# MCU.net
KiCad netlist of a schematic drawn in Altium Designer
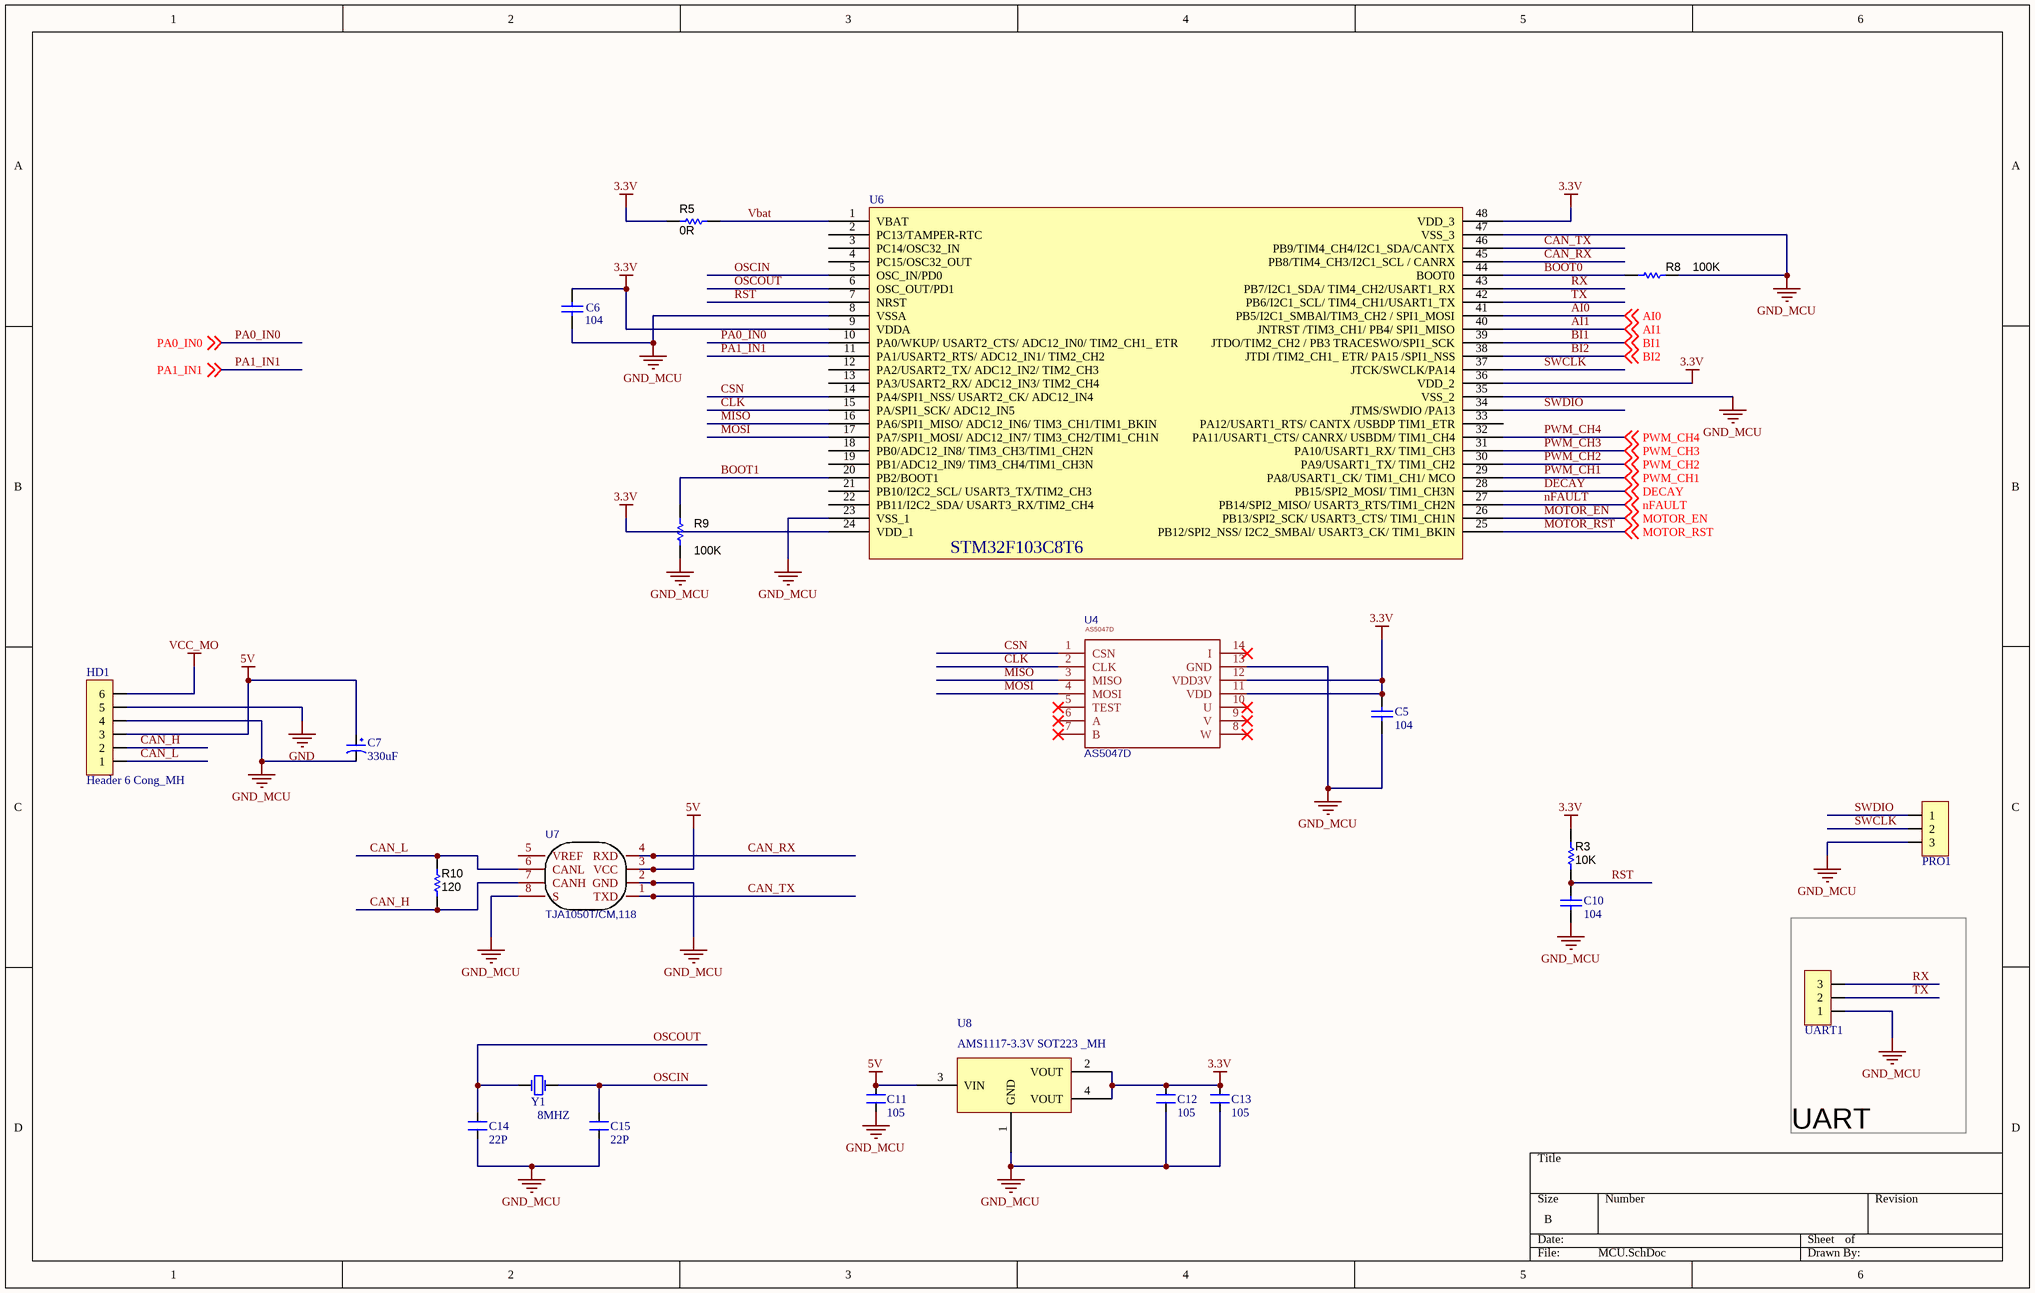
[diagram p0: MCU.SchDoc]

(export (version "E")
  (design (tool "Eeschema 10.0.6"))
  (components
    (comp (ref "C5")
      (value "104")
      (footprint "0805_HV")
      (description "Ceramic Chip Capacitor - Standard")
      (fields (field (name "PUBLISHER") "Altium Limited"))
      (libsource (lib "mySch") (part "Capacitor 0805"))
    )
    (comp (ref "C6")
      (value "104")
      (footprint "0805_HV")
      (description "Ceramic Chip Capacitor - Standard")
      (fields (field (name "PUBLISHER") "Altium Limited"))
      (libsource (lib "mySch") (part "Capacitor 0805"))
    )
    (comp (ref "C7")
      (value "330uF")
      (footprint "TU_NHOM_220uF_25V_MH")
      (description "TU_NHOM_330uF_16V_MH")
      (libsource (lib "MH_DA_THU_VIEN_16122016") (part "TU_NHOM_330uF_16V_MH"))
    )
    (comp (ref "C10")
      (value "104")
      (footprint "0805_HV")
      (description "Ceramic Chip Capacitor - Standard")
      (fields (field (name "PUBLISHER") "Altium Limited"))
      (libsource (lib "mySch") (part "Capacitor 0805"))
    )
    (comp (ref "C11")
      (value "105")
      (footprint "0805_HV")
      (description "Cap SMD")
      (libsource (lib "hatcatbietbay") (part "CM"))
    )
    (comp (ref "C12")
      (value "105")
      (footprint "0805_HV")
      (description "Cap SMD")
      (libsource (lib "hatcatbietbay") (part "CM"))
    )
    (comp (ref "C13")
      (value "105")
      (footprint "0805_HV")
      (description "Cap SMD")
      (libsource (lib "hatcatbietbay") (part "CM"))
    )
    (comp (ref "C14")
      (value "22P")
      (footprint "0805_HV")
      (description "Cap SMD")
      (libsource (lib "hatcatbietbay") (part "CM"))
    )
    (comp (ref "C15")
      (value "22P")
      (footprint "0805_HV")
      (description "Cap SMD")
      (libsource (lib "hatcatbietbay") (part "CM"))
    )
    (comp (ref "HD1")
      (value "Header 6 Cong_MH")
      (footprint "HEADER 6 CONG")
      (description "Header 6P XH2.54 cong")
      (libsource (lib "MH_DA_THU_VIEN_16122016") (part "Header 6 Cong_MH"))
    )
    (comp (ref "PRO1")
      (value "Header 3_MH")
      (footprint "HEADER 3")
      (description "Header 3P XH2.54 thẳng")
      (libsource (lib "") (part "Header 3_MH_1"))
    )
    (comp (ref "R3")
      (value "10K")
      (footprint "0805_HV")
      (description "RES, 100, 1%, 0.1 W, 0402")
      (fields
        (field (name "PARTNUMBER") "ERJ-2RKF1000X")
        (field (name "MANUFACTURER") "Panasonic")
        (field (name "PUBLISHER") "Texas Instruments")
      )
      (libsource (lib "mySch") (part "R nho"))
    )
    (comp (ref "R5")
      (value "0R")
      (footprint "0805_HV")
      (description "RES, 100, 1%, 0.1 W, 0402")
      (fields
        (field (name "PARTNUMBER") "ERJ-2RKF1000X")
        (field (name "MANUFACTURER") "Panasonic")
        (field (name "PUBLISHER") "Texas Instruments")
      )
      (libsource (lib "mySch") (part "R nho"))
    )
    (comp (ref "R8")
      (value "100K")
      (footprint "0805_HV")
      (description "RES, 100, 1%, 0.1 W, 0402")
      (fields
        (field (name "PARTNUMBER") "ERJ-2RKF1000X")
        (field (name "MANUFACTURER") "Panasonic")
        (field (name "PUBLISHER") "Texas Instruments")
      )
      (libsource (lib "mySch") (part "R nho"))
    )
    (comp (ref "R9")
      (value "100K")
      (footprint "0805_HV")
      (description "RES, 100, 1%, 0.1 W, 0402")
      (fields
        (field (name "PARTNUMBER") "ERJ-2RKF1000X")
        (field (name "MANUFACTURER") "Panasonic")
        (field (name "PUBLISHER") "Texas Instruments")
      )
      (libsource (lib "mySch") (part "R nho"))
    )
    (comp (ref "R10")
      (value "120")
      (footprint "0805_HV")
      (description "RES, 100, 1%, 0.1 W, 0402")
      (fields
        (field (name "PARTNUMBER") "ERJ-2RKF1000X")
        (field (name "MANUFACTURER") "Panasonic")
        (field (name "PUBLISHER") "Texas Instruments")
      )
      (libsource (lib "mySch") (part "R nho"))
    )
    (comp (ref "U4")
      (value "AS5047D")
      (footprint "TSSOP14")
      (fields (field (name "BOM_MANUFACTURER PART") "?"))
      (libsource (lib "mySch") (part "AS5047D"))
    )
    (comp (ref "U6")
      (value "STM32F103C8T6 LQFP48 _MH")
      (footprint "LQFP48")
      (libsource (lib "MH_DA_THU_VIEN_16122016") (part "STM32F103C8T6 LQFP48 _MH"))
    )
    (comp (ref "U7")
      (value "TJA1050T/CM,118")
      (footprint "SOP 8")
      (fields (field (name "BOM_SUPPLIER PART") "C6952"))
      (libsource (lib "Schlib1") (part "TJA1050T/CM,118"))
    )
    (comp (ref "U8")
      (value "AMS1117-3.3V SOT223 _MH")
      (footprint "SOT223")
      (libsource (lib "MH_DA_THU_VIEN_16122016") (part "AMS1117-3.3V SOT223 _MH"))
    )
    (comp (ref "UART1")
      (value "Header 3_MH")
      (footprint "HEADER 3")
      (description "Header 3P XH2.54 thẳng")
      (libsource (lib "MH_DA_THU_VIEN_16122016") (part "Header 3_MH"))
    )
    (comp (ref "Y1")
      (value "8MHZ")
      (footprint "XT2")
      (description "Crystal Oscillator")
      (fields (field (name "PUBLISHER") "Altium Limited"))
      (libsource (lib "MH_DA_THU_VIEN_16122016") (part "CRYSTAL_49S DIP_MH"))
    )
  )
  (nets
    (net (code "1") (name "/BOOT0") (class "Default")
      (node (ref "R8") (pin "2") (pinfunction "2_2") (pintype "passive"))
      (node (ref "U6") (pin "44") (pinfunction "BOOT0_44") (pintype "passive"))
    )
    (net (code "2") (name "/BOOT1") (class "Default")
      (node (ref "R9") (pin "1") (pinfunction "1_1") (pintype "passive"))
      (node (ref "U6") (pin "20") (pinfunction "PB2/BOOT1_20") (pintype "passive"))
    )
    (net (code "3") (name "/CAN_H") (class "Default")
      (node (ref "HD1") (pin "2") (pinfunction "2_2") (pintype "passive"))
      (node (ref "R10") (pin "2") (pinfunction "2_2") (pintype "passive"))
      (node (ref "U7") (pin "7") (pinfunction "CANH_7") (pintype "passive"))
    )
    (net (code "4") (name "/CAN_L") (class "Default")
      (node (ref "HD1") (pin "1") (pinfunction "1_1") (pintype "passive"))
      (node (ref "R10") (pin "1") (pinfunction "1_1") (pintype "passive"))
      (node (ref "U7") (pin "6") (pinfunction "CANL_6") (pintype "passive"))
    )
    (net (code "5") (name "/CAN_RX") (class "Default")
      (node (ref "U6") (pin "45") (pinfunction "PB8/TIM4_CH3/I2C1_SCL_/_CANRX_45") (pintype "passive"))
      (node (ref "U7") (pin "4") (pinfunction "RXD_4") (pintype "passive"))
    )
    (net (code "6") (name "/CAN_TX") (class "Default")
      (node (ref "U6") (pin "46") (pinfunction "PB9/TIM4_CH4/I2C1_SDA/CANTX_46") (pintype "passive"))
      (node (ref "U7") (pin "1") (pinfunction "TXD_1") (pintype "passive"))
    )
    (net (code "7") (name "/CLK") (class "Default")
      (node (ref "U4") (pin "2") (pinfunction "CLK_2") (pintype "passive"))
      (node (ref "U6") (pin "15") (pinfunction "PA/SPI1_SCK/_ADC12_IN5_15") (pintype "passive"))
    )
    (net (code "8") (name "/CSN") (class "Default")
      (node (ref "U4") (pin "1") (pinfunction "CSN_1") (pintype "passive"))
      (node (ref "U6") (pin "14") (pinfunction "PA4/SPI1_NSS/_USART2_CK/_ADC12_IN4_14") (pintype "passive"))
    )
    (net (code "9") (name "/MISO") (class "Default")
      (node (ref "U4") (pin "3") (pinfunction "MISO_3") (pintype "passive"))
      (node (ref "U6") (pin "16") (pinfunction "PA6/SPI1_MISO/_ADC12_IN6/_TIM3_CH1/TIM1_BKIN_16") (pintype "passive"))
    )
    (net (code "10") (name "/MOSI") (class "Default")
      (node (ref "U4") (pin "4") (pinfunction "MOSI_4") (pintype "passive"))
      (node (ref "U6") (pin "17") (pinfunction "PA7/SPI1_MOSI/_ADC12_IN7/_TIM3_CH2/TIM1_CH1N_17") (pintype "passive"))
    )
    (net (code "11") (name "/OSCIN") (class "Default")
      (node (ref "C15") (pin "2") (pinfunction "2_2") (pintype "passive"))
      (node (ref "U6") (pin "5") (pinfunction "OSC_IN/PD0_5") (pintype "passive"))
      (node (ref "Y1") (pin "2") (pinfunction "OSC2_2") (pintype "passive"))
    )
    (net (code "12") (name "/OSCOUT") (class "Default")
      (node (ref "C14") (pin "2") (pinfunction "2_2") (pintype "passive"))
      (node (ref "U6") (pin "6") (pinfunction "OSC_OUT/PD1_6") (pintype "passive"))
      (node (ref "Y1") (pin "1") (pinfunction "OSC1_1") (pintype "passive"))
    )
    (net (code "13") (name "/RST") (class "Default")
      (node (ref "C10") (pin "2") (pinfunction "2_2") (pintype "passive"))
      (node (ref "R3") (pin "1") (pinfunction "1_1") (pintype "passive"))
      (node (ref "U6") (pin "7") (pinfunction "NRST_7") (pintype "passive"))
    )
    (net (code "14") (name "/RX") (class "Default")
      (node (ref "U6") (pin "43") (pinfunction "PB7/I2C1_SDA/_TIM4_CH2/USART1_RX_43") (pintype "passive"))
      (node (ref "UART1") (pin "3") (pinfunction "3_3") (pintype "passive"))
    )
    (net (code "15") (name "/SWCLK") (class "Default")
      (node (ref "PRO1") (pin "2") (pinfunction "2_2") (pintype "passive"))
      (node (ref "U6") (pin "37") (pinfunction "JTCK/SWCLK/PA14_37") (pintype "passive"))
    )
    (net (code "16") (name "/SWDIO") (class "Default")
      (node (ref "PRO1") (pin "1") (pinfunction "1_1") (pintype "passive"))
      (node (ref "U6") (pin "34") (pinfunction "JTMS/SWDIO_/PA13_34") (pintype "passive"))
    )
    (net (code "17") (name "/TX") (class "Default")
      (node (ref "U6") (pin "42") (pinfunction "PB6/I2C1_SCL/_TIM4_CH1/USART1_TX_42") (pintype "passive"))
      (node (ref "UART1") (pin "2") (pinfunction "2_2") (pintype "passive"))
    )
    (net (code "18") (name "/Vbat") (class "Default")
      (node (ref "R5") (pin "1") (pinfunction "1_1") (pintype "passive"))
      (node (ref "U6") (pin "1") (pinfunction "VBAT_1") (pintype "passive"))
    )
    (net (code "19") (name "3.3V") (class "Default")
      (node (ref "C12") (pin "2") (pinfunction "2_2") (pintype "passive"))
      (node (ref "C13") (pin "2") (pinfunction "2_2") (pintype "passive"))
      (node (ref "C5") (pin "2") (pinfunction "2_2") (pintype "passive"))
      (node (ref "C6") (pin "2") (pinfunction "2_2") (pintype "passive"))
      (node (ref "R3") (pin "2") (pinfunction "2_2") (pintype "passive"))
      (node (ref "R5") (pin "2") (pinfunction "2_2") (pintype "passive"))
      (node (ref "U4") (pin "11") (pinfunction "VDD_11") (pintype "passive"))
      (node (ref "U4") (pin "12") (pinfunction "VDD3V_12") (pintype "passive"))
      (node (ref "U6") (pin "24") (pinfunction "VDD_1_24") (pintype "passive"))
      (node (ref "U6") (pin "36") (pinfunction "VDD_2_36") (pintype "passive"))
      (node (ref "U6") (pin "48") (pinfunction "VDD_3_48") (pintype "passive"))
      (node (ref "U6") (pin "9") (pinfunction "VDDA_9") (pintype "passive"))
      (node (ref "U8") (pin "2") (pinfunction "VOUT_2") (pintype "passive"))
      (node (ref "U8") (pin "4") (pinfunction "VOUT_4") (pintype "passive"))
    )
    (net (code "20") (name "5V") (class "Default")
      (node (ref "C11") (pin "2") (pinfunction "2_2") (pintype "passive"))
      (node (ref "C7") (pin "1") (pinfunction "1_1") (pintype "passive"))
      (node (ref "HD1") (pin "3") (pinfunction "3_3") (pintype "passive"))
      (node (ref "U7") (pin "3") (pinfunction "VCC_3") (pintype "passive"))
      (node (ref "U8") (pin "3") (pinfunction "VIN_3") (pintype "passive"))
    )
    (net (code "21") (name "AI0") (class "Default")
      (node (ref "U6") (pin "41") (pinfunction "PB5/I2C1_SMBAl/TIM3_CH2_/_SPI1_MOSI_41") (pintype "passive"))
    )
    (net (code "22") (name "AI1") (class "Default")
      (node (ref "U6") (pin "40") (pinfunction "JNTRST_/TIM3_CH1/_PB4/_SPI1_MISO_40") (pintype "passive"))
    )
    (net (code "23") (name "BI1") (class "Default")
      (node (ref "U6") (pin "39") (pinfunction "JTDO/TIM2_CH2_/_PB3_TRACESWO/SPI1_SCK_39") (pintype "passive"))
    )
    (net (code "24") (name "BI2") (class "Default")
      (node (ref "U6") (pin "38") (pinfunction "JTDI_/TIM2_CH1__ETR/_PA15_/SPI1_NSS_38") (pintype "passive"))
    )
    (net (code "25") (name "DECAY") (class "Default")
      (node (ref "U6") (pin "28") (pinfunction "PB15/SPI2_MOSI/_TIM1_CH3N_28") (pintype "passive"))
    )
    (net (code "26") (name "GND") (class "Default")
      (node (ref "HD1") (pin "5") (pinfunction "5_5") (pintype "passive"))
    )
    (net (code "27") (name "GND_MCU") (class "Default")
      (node (ref "C10") (pin "1") (pinfunction "1_1") (pintype "passive"))
      (node (ref "C11") (pin "1") (pinfunction "1_1") (pintype "passive"))
      (node (ref "C12") (pin "1") (pinfunction "1_1") (pintype "passive"))
      (node (ref "C13") (pin "1") (pinfunction "1_1") (pintype "passive"))
      (node (ref "C14") (pin "1") (pinfunction "1_1") (pintype "passive"))
      (node (ref "C15") (pin "1") (pinfunction "1_1") (pintype "passive"))
      (node (ref "C5") (pin "1") (pinfunction "1_1") (pintype "passive"))
      (node (ref "C6") (pin "1") (pinfunction "1_1") (pintype "passive"))
      (node (ref "C7") (pin "2") (pinfunction "2_2") (pintype "passive"))
      (node (ref "HD1") (pin "4") (pinfunction "4_4") (pintype "passive"))
      (node (ref "PRO1") (pin "3") (pinfunction "3_3") (pintype "passive"))
      (node (ref "R8") (pin "1") (pinfunction "1_1") (pintype "passive"))
      (node (ref "R9") (pin "2") (pinfunction "2_2") (pintype "passive"))
      (node (ref "U4") (pin "13") (pinfunction "GND_13") (pintype "passive"))
      (node (ref "U6") (pin "23") (pinfunction "VSS_1_23") (pintype "passive"))
      (node (ref "U6") (pin "35") (pinfunction "VSS_2_35") (pintype "passive"))
      (node (ref "U6") (pin "47") (pinfunction "VSS_3_47") (pintype "passive"))
      (node (ref "U6") (pin "8") (pinfunction "VSSA_8") (pintype "passive"))
      (node (ref "U7") (pin "2") (pinfunction "GND_2") (pintype "passive"))
      (node (ref "U7") (pin "8") (pinfunction "S_8") (pintype "passive"))
      (node (ref "U8") (pin "1") (pinfunction "GND_1") (pintype "passive"))
      (node (ref "UART1") (pin "1") (pinfunction "1_1") (pintype "passive"))
    )
    (net (code "28") (name "MOTOR_EN") (class "Default")
      (node (ref "U6") (pin "26") (pinfunction "PB13/SPI2_SCK/_USART3_CTS/_TIM1_CH1N_26") (pintype "passive"))
    )
    (net (code "29") (name "MOTOR_RST") (class "Default")
      (node (ref "U6") (pin "25") (pinfunction "PB12/SPI2_NSS/_I2C2_SMBAl/_USART3_CK/_TIM1_BKIN_25") (pintype "passive"))
    )
    (net (code "30") (name "PA0_IN0") (class "Default")
      (node (ref "U6") (pin "10") (pinfunction "PA0/WKUP/_USART2_CTS/_ADC12_IN0/_TIM2_CH1__ETR_10") (pintype "passive"))
    )
    (net (code "31") (name "PA1_IN1") (class "Default")
      (node (ref "U6") (pin "11") (pinfunction "PA1/USART2_RTS/_ADC12_IN1/_TIM2_CH2_11") (pintype "passive"))
    )
    (net (code "32") (name "PWM_CH1") (class "Default")
      (node (ref "U6") (pin "29") (pinfunction "PA8/USART1_CK/_TIM1_CH1/_MCO_29") (pintype "passive"))
    )
    (net (code "33") (name "PWM_CH2") (class "Default")
      (node (ref "U6") (pin "30") (pinfunction "PA9/USART1_TX/_TIM1_CH2_30") (pintype "passive"))
    )
    (net (code "34") (name "PWM_CH3") (class "Default")
      (node (ref "U6") (pin "31") (pinfunction "PA10/USART1_RX/_TIM1_CH3_31") (pintype "passive"))
    )
    (net (code "35") (name "PWM_CH4") (class "Default")
      (node (ref "U6") (pin "32") (pinfunction "PA11/USART1_CTS/_CANRX/_USBDM/_TIM1_CH4_32") (pintype "passive"))
    )
    (net (code "36") (name "VCC_MO") (class "Default")
      (node (ref "HD1") (pin "6") (pinfunction "6_6") (pintype "passive"))
    )
    (net (code "37") (name "nFAULT") (class "Default")
      (node (ref "U6") (pin "27") (pinfunction "PB14/SPI2_MISO/_USART3_RTS/TIM1_CH2N_27") (pintype "passive"))
    )
    (net (code "38") (name "unconnected-(U4-A-Pad6)") (class "Default")
      (node (ref "U4") (pin "6") (pinfunction "A_6") (pintype "passive+no_connect"))
    )
    (net (code "39") (name "unconnected-(U4-B-Pad7)") (class "Default")
      (node (ref "U4") (pin "7") (pinfunction "B_7") (pintype "passive+no_connect"))
    )
    (net (code "40") (name "unconnected-(U4-I-Pad14)") (class "Default")
      (node (ref "U4") (pin "14") (pinfunction "I_14") (pintype "passive+no_connect"))
    )
    (net (code "41") (name "unconnected-(U4-TEST-Pad5)") (class "Default")
      (node (ref "U4") (pin "5") (pinfunction "TEST_5") (pintype "passive+no_connect"))
    )
    (net (code "42") (name "unconnected-(U4-U-Pad10)") (class "Default")
      (node (ref "U4") (pin "10") (pinfunction "U_10") (pintype "passive+no_connect"))
    )
    (net (code "43") (name "unconnected-(U4-V-Pad9)") (class "Default")
      (node (ref "U4") (pin "9") (pinfunction "V_9") (pintype "passive+no_connect"))
    )
    (net (code "44") (name "unconnected-(U4-W-Pad8)") (class "Default")
      (node (ref "U4") (pin "8") (pinfunction "W_8") (pintype "passive+no_connect"))
    )
    (net (code "45") (name "unconnected-(U6-PA2{slash}USART2_TX{slash}_ADC12_IN2{slash}_TIM2_CH3-Pad12)") (class "Default")
      (node (ref "U6") (pin "12") (pinfunction "PA2/USART2_TX/_ADC12_IN2/_TIM2_CH3_12") (pintype "passive"))
    )
    (net (code "46") (name "unconnected-(U6-PA3{slash}USART2_RX{slash}_ADC12_IN3{slash}_TIM2_CH4-Pad13)") (class "Default")
      (node (ref "U6") (pin "13") (pinfunction "PA3/USART2_RX/_ADC12_IN3/_TIM2_CH4_13") (pintype "passive"))
    )
    (net (code "47") (name "unconnected-(U6-PA12{slash}USART1_RTS{slash}_CANTX_{slash}USBDP_TIM1_ETR-Pad33)") (class "Default")
      (node (ref "U6") (pin "33") (pinfunction "PA12/USART1_RTS/_CANTX_/USBDP_TIM1_ETR_33") (pintype "passive"))
    )
    (net (code "48") (name "unconnected-(U6-PB0{slash}ADC12_IN8{slash}_TIM3_CH3{slash}TIM1_CH2N-Pad18)") (class "Default")
      (node (ref "U6") (pin "18") (pinfunction "PB0/ADC12_IN8/_TIM3_CH3/TIM1_CH2N_18") (pintype "passive"))
    )
    (net (code "49") (name "unconnected-(U6-PB1{slash}ADC12_IN9{slash}_TIM3_CH4{slash}TIM1_CH3N-Pad19)") (class "Default")
      (node (ref "U6") (pin "19") (pinfunction "PB1/ADC12_IN9/_TIM3_CH4/TIM1_CH3N_19") (pintype "passive"))
    )
    (net (code "50") (name "unconnected-(U6-PB10{slash}I2C2_SCL{slash}_USART3_TX{slash}TIM2_CH3-Pad21)") (class "Default")
      (node (ref "U6") (pin "21") (pinfunction "PB10/I2C2_SCL/_USART3_TX/TIM2_CH3_21") (pintype "passive"))
    )
    (net (code "51") (name "unconnected-(U6-PB11{slash}I2C2_SDA{slash}_USART3_RX{slash}TIM2_CH4-Pad22)") (class "Default")
      (node (ref "U6") (pin "22") (pinfunction "PB11/I2C2_SDA/_USART3_RX/TIM2_CH4_22") (pintype "passive"))
    )
    (net (code "52") (name "unconnected-(U6-PC13{slash}TAMPER-RTC-Pad2)") (class "Default")
      (node (ref "U6") (pin "2") (pinfunction "PC13/TAMPER-RTC_2") (pintype "passive"))
    )
    (net (code "53") (name "unconnected-(U6-PC14{slash}OSC32_IN-Pad3)") (class "Default")
      (node (ref "U6") (pin "3") (pinfunction "PC14/OSC32_IN_3") (pintype "passive"))
    )
    (net (code "54") (name "unconnected-(U6-PC15{slash}OSC32_OUT-Pad4)") (class "Default")
      (node (ref "U6") (pin "4") (pinfunction "PC15/OSC32_OUT_4") (pintype "passive"))
    )
    (net (code "55") (name "unconnected-(U7-VREF-Pad5)") (class "Default")
      (node (ref "U7") (pin "5") (pinfunction "VREF_5") (pintype "passive"))
    )
  )
)
